# Crockoft-Walton_01.net
KiCad netlist of a schematic drawn in EAGLE
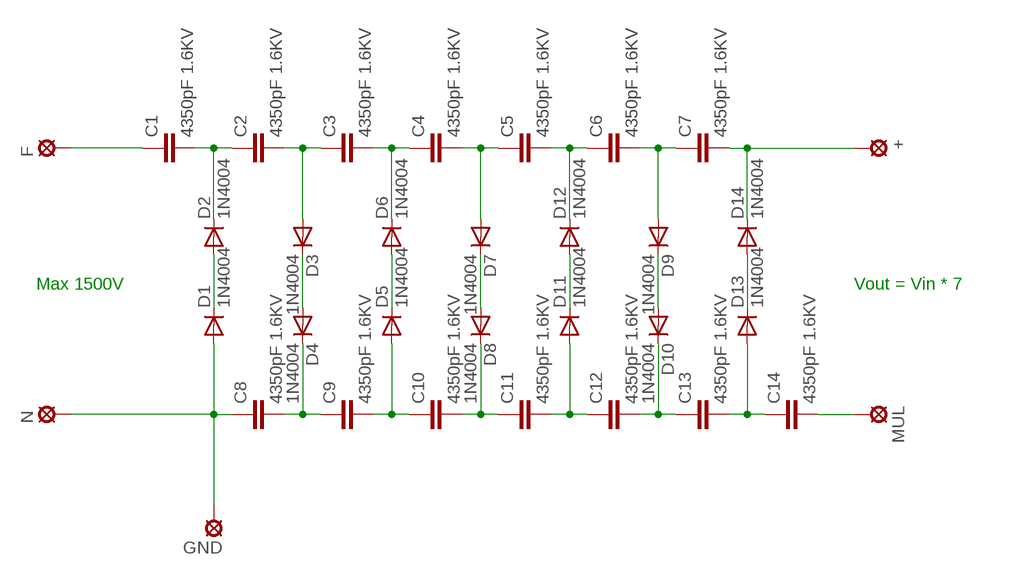
[diagram p0: schematic, sheet 1]

(export (version "E")
  (design (tool "Eeschema 10.0.6"))
  (components
    (comp (ref "+")
      (value "LSP13")
      (footprint "eagle-import:LSP13")
      (libsource (lib "eagle-import") (part "LSP13"))
    )
    (comp (ref "C1")
      (value "4350pF 1.6KV")
      (footprint "eagle-import:C225-074X268")
      (libsource (lib "eagle-import") (part "C-EU225-074X268"))
    )
    (comp (ref "C2")
      (value "4350pF 1.6KV")
      (footprint "eagle-import:C225-074X268")
      (libsource (lib "eagle-import") (part "C-EU225-074X268"))
    )
    (comp (ref "C3")
      (value "4350pF 1.6KV")
      (footprint "eagle-import:C225-074X268")
      (libsource (lib "eagle-import") (part "C-EU225-074X268"))
    )
    (comp (ref "C4")
      (value "4350pF 1.6KV")
      (footprint "eagle-import:C225-074X268")
      (libsource (lib "eagle-import") (part "C-EU225-074X268"))
    )
    (comp (ref "C5")
      (value "4350pF 1.6KV")
      (footprint "eagle-import:C225-074X268")
      (libsource (lib "eagle-import") (part "C-EU225-074X268"))
    )
    (comp (ref "C6")
      (value "4350pF 1.6KV")
      (footprint "eagle-import:C225-074X268")
      (libsource (lib "eagle-import") (part "C-EU225-074X268"))
    )
    (comp (ref "C7")
      (value "4350pF 1.6KV")
      (footprint "eagle-import:C225-074X268")
      (libsource (lib "eagle-import") (part "C-EU225-074X268"))
    )
    (comp (ref "C8")
      (value "4350pF 1.6KV")
      (footprint "eagle-import:C225-074X268")
      (libsource (lib "eagle-import") (part "C-EU225-074X268"))
    )
    (comp (ref "C9")
      (value "4350pF 1.6KV")
      (footprint "eagle-import:C225-074X268")
      (libsource (lib "eagle-import") (part "C-EU225-074X268"))
    )
    (comp (ref "C10")
      (value "4350pF 1.6KV")
      (footprint "eagle-import:C225-074X268")
      (libsource (lib "eagle-import") (part "C-EU225-074X268"))
    )
    (comp (ref "C11")
      (value "4350pF 1.6KV")
      (footprint "eagle-import:C225-074X268")
      (libsource (lib "eagle-import") (part "C-EU225-074X268"))
    )
    (comp (ref "C12")
      (value "4350pF 1.6KV")
      (footprint "eagle-import:C225-074X268")
      (libsource (lib "eagle-import") (part "C-EU225-074X268"))
    )
    (comp (ref "C13")
      (value "4350pF 1.6KV")
      (footprint "eagle-import:C225-074X268")
      (libsource (lib "eagle-import") (part "C-EU225-074X268"))
    )
    (comp (ref "C14")
      (value "4350pF 1.6KV")
      (footprint "eagle-import:C225-074X268")
      (libsource (lib "eagle-import") (part "C-EU225-074X268"))
    )
    (comp (ref "D1")
      (value "1N4004")
      (footprint "eagle-import:DO41-10")
      (libsource (lib "eagle-import") (part "1N4004"))
    )
    (comp (ref "D2")
      (value "1N4004")
      (footprint "eagle-import:DO41-10")
      (libsource (lib "eagle-import") (part "1N4004"))
    )
    (comp (ref "D3")
      (value "1N4004")
      (footprint "eagle-import:DO41-10")
      (libsource (lib "eagle-import") (part "1N4004"))
    )
    (comp (ref "D4")
      (value "1N4004")
      (footprint "eagle-import:DO41-10")
      (libsource (lib "eagle-import") (part "1N4004"))
    )
    (comp (ref "D5")
      (value "1N4004")
      (footprint "eagle-import:DO41-10")
      (libsource (lib "eagle-import") (part "1N4004"))
    )
    (comp (ref "D6")
      (value "1N4004")
      (footprint "eagle-import:DO41-10")
      (libsource (lib "eagle-import") (part "1N4004"))
    )
    (comp (ref "D7")
      (value "1N4004")
      (footprint "eagle-import:DO41-10")
      (libsource (lib "eagle-import") (part "1N4004"))
    )
    (comp (ref "D8")
      (value "1N4004")
      (footprint "eagle-import:DO41-10")
      (libsource (lib "eagle-import") (part "1N4004"))
    )
    (comp (ref "D9")
      (value "1N4004")
      (footprint "eagle-import:DO41-10")
      (libsource (lib "eagle-import") (part "1N4004"))
    )
    (comp (ref "D10")
      (value "1N4004")
      (footprint "eagle-import:DO41-10")
      (libsource (lib "eagle-import") (part "1N4004"))
    )
    (comp (ref "D11")
      (value "1N4004")
      (footprint "eagle-import:DO41-10")
      (libsource (lib "eagle-import") (part "1N4004"))
    )
    (comp (ref "D12")
      (value "1N4004")
      (footprint "eagle-import:DO41-10")
      (libsource (lib "eagle-import") (part "1N4004"))
    )
    (comp (ref "D13")
      (value "1N4004")
      (footprint "eagle-import:DO41-10")
      (libsource (lib "eagle-import") (part "1N4004"))
    )
    (comp (ref "D14")
      (value "1N4004")
      (footprint "eagle-import:DO41-10")
      (libsource (lib "eagle-import") (part "1N4004"))
    )
    (comp (ref "F")
      (value "LSP13")
      (footprint "eagle-import:LSP13")
      (libsource (lib "eagle-import") (part "LSP13"))
    )
    (comp (ref "GND")
      (value "LSP13")
      (footprint "eagle-import:LSP13")
      (libsource (lib "eagle-import") (part "LSP13"))
    )
    (comp (ref "MUL")
      (value "LSP13")
      (footprint "eagle-import:LSP13")
      (libsource (lib "eagle-import") (part "LSP13"))
    )
    (comp (ref "N")
      (value "LSP13")
      (footprint "eagle-import:LSP13")
      (libsource (lib "eagle-import") (part "LSP13"))
    )
  )
  (nets
    (net (code "1") (name "Net-(+-PadMP)") (class "Default")
      (node (ref "+") (pin "MP") (pinfunction "MP_MP") (pintype "passive"))
      (node (ref "C7") (pin "2") (pinfunction "2_2") (pintype "passive"))
      (node (ref "D14") (pin "C") (pinfunction "C_C") (pintype "passive"))
    )
    (net (code "2") (name "Net-(C1-Pad1)") (class "Default")
      (node (ref "C1") (pin "1") (pinfunction "1_1") (pintype "passive"))
      (node (ref "F") (pin "MP") (pinfunction "MP_MP") (pintype "passive"))
    )
    (net (code "3") (name "Net-(C1-Pad2)") (class "Default")
      (node (ref "C1") (pin "2") (pinfunction "2_2") (pintype "passive"))
      (node (ref "C2") (pin "1") (pinfunction "1_1") (pintype "passive"))
      (node (ref "D2") (pin "C") (pinfunction "C_C") (pintype "passive"))
    )
    (net (code "4") (name "Net-(C2-Pad2)") (class "Default")
      (node (ref "C2") (pin "2") (pinfunction "2_2") (pintype "passive"))
      (node (ref "C3") (pin "1") (pinfunction "1_1") (pintype "passive"))
      (node (ref "D3") (pin "A") (pinfunction "A_A") (pintype "passive"))
    )
    (net (code "5") (name "Net-(C3-Pad2)") (class "Default")
      (node (ref "C3") (pin "2") (pinfunction "2_2") (pintype "passive"))
      (node (ref "C4") (pin "1") (pinfunction "1_1") (pintype "passive"))
      (node (ref "D6") (pin "C") (pinfunction "C_C") (pintype "passive"))
    )
    (net (code "6") (name "Net-(C4-Pad2)") (class "Default")
      (node (ref "C4") (pin "2") (pinfunction "2_2") (pintype "passive"))
      (node (ref "C5") (pin "1") (pinfunction "1_1") (pintype "passive"))
      (node (ref "D7") (pin "A") (pinfunction "A_A") (pintype "passive"))
    )
    (net (code "7") (name "Net-(C5-Pad2)") (class "Default")
      (node (ref "C5") (pin "2") (pinfunction "2_2") (pintype "passive"))
      (node (ref "C6") (pin "1") (pinfunction "1_1") (pintype "passive"))
      (node (ref "D12") (pin "C") (pinfunction "C_C") (pintype "passive"))
    )
    (net (code "8") (name "Net-(C6-Pad2)") (class "Default")
      (node (ref "C6") (pin "2") (pinfunction "2_2") (pintype "passive"))
      (node (ref "C7") (pin "1") (pinfunction "1_1") (pintype "passive"))
      (node (ref "D9") (pin "A") (pinfunction "A_A") (pintype "passive"))
    )
    (net (code "9") (name "Net-(C8-Pad1)") (class "Default")
      (node (ref "C8") (pin "1") (pinfunction "1_1") (pintype "passive"))
      (node (ref "D1") (pin "A") (pinfunction "A_A") (pintype "passive"))
      (node (ref "GND") (pin "MP") (pinfunction "MP_MP") (pintype "passive"))
      (node (ref "N") (pin "MP") (pinfunction "MP_MP") (pintype "passive"))
    )
    (net (code "10") (name "Net-(C8-Pad2)") (class "Default")
      (node (ref "C8") (pin "2") (pinfunction "2_2") (pintype "passive"))
      (node (ref "C9") (pin "1") (pinfunction "1_1") (pintype "passive"))
      (node (ref "D4") (pin "C") (pinfunction "C_C") (pintype "passive"))
    )
    (net (code "11") (name "Net-(C10-Pad1)") (class "Default")
      (node (ref "C10") (pin "1") (pinfunction "1_1") (pintype "passive"))
      (node (ref "C9") (pin "2") (pinfunction "2_2") (pintype "passive"))
      (node (ref "D5") (pin "A") (pinfunction "A_A") (pintype "passive"))
    )
    (net (code "12") (name "Net-(C10-Pad2)") (class "Default")
      (node (ref "C10") (pin "2") (pinfunction "2_2") (pintype "passive"))
      (node (ref "C11") (pin "1") (pinfunction "1_1") (pintype "passive"))
      (node (ref "D8") (pin "C") (pinfunction "C_C") (pintype "passive"))
    )
    (net (code "13") (name "Net-(C11-Pad2)") (class "Default")
      (node (ref "C11") (pin "2") (pinfunction "2_2") (pintype "passive"))
      (node (ref "C12") (pin "1") (pinfunction "1_1") (pintype "passive"))
      (node (ref "D11") (pin "A") (pinfunction "A_A") (pintype "passive"))
    )
    (net (code "14") (name "Net-(C12-Pad2)") (class "Default")
      (node (ref "C12") (pin "2") (pinfunction "2_2") (pintype "passive"))
      (node (ref "C13") (pin "1") (pinfunction "1_1") (pintype "passive"))
      (node (ref "D10") (pin "C") (pinfunction "C_C") (pintype "passive"))
    )
    (net (code "15") (name "Net-(C13-Pad2)") (class "Default")
      (node (ref "C13") (pin "2") (pinfunction "2_2") (pintype "passive"))
      (node (ref "C14") (pin "1") (pinfunction "1_1") (pintype "passive"))
      (node (ref "D13") (pin "A") (pinfunction "A_A") (pintype "passive"))
    )
    (net (code "16") (name "Net-(C14-Pad2)") (class "Default")
      (node (ref "C14") (pin "2") (pinfunction "2_2") (pintype "passive"))
      (node (ref "MUL") (pin "MP") (pinfunction "MP_MP") (pintype "passive"))
    )
    (net (code "17") (name "Net-(D1-PadC)") (class "Default")
      (node (ref "D1") (pin "C") (pinfunction "C_C") (pintype "passive"))
      (node (ref "D2") (pin "A") (pinfunction "A_A") (pintype "passive"))
    )
    (net (code "18") (name "Net-(D3-PadC)") (class "Default")
      (node (ref "D3") (pin "C") (pinfunction "C_C") (pintype "passive"))
      (node (ref "D4") (pin "A") (pinfunction "A_A") (pintype "passive"))
    )
    (net (code "19") (name "Net-(D5-PadC)") (class "Default")
      (node (ref "D5") (pin "C") (pinfunction "C_C") (pintype "passive"))
      (node (ref "D6") (pin "A") (pinfunction "A_A") (pintype "passive"))
    )
    (net (code "20") (name "Net-(D7-PadC)") (class "Default")
      (node (ref "D7") (pin "C") (pinfunction "C_C") (pintype "passive"))
      (node (ref "D8") (pin "A") (pinfunction "A_A") (pintype "passive"))
    )
    (net (code "21") (name "Net-(D10-PadA)") (class "Default")
      (node (ref "D10") (pin "A") (pinfunction "A_A") (pintype "passive"))
      (node (ref "D9") (pin "C") (pinfunction "C_C") (pintype "passive"))
    )
    (net (code "22") (name "Net-(D11-PadC)") (class "Default")
      (node (ref "D11") (pin "C") (pinfunction "C_C") (pintype "passive"))
      (node (ref "D12") (pin "A") (pinfunction "A_A") (pintype "passive"))
    )
    (net (code "23") (name "Net-(D13-PadC)") (class "Default")
      (node (ref "D13") (pin "C") (pinfunction "C_C") (pintype "passive"))
      (node (ref "D14") (pin "A") (pinfunction "A_A") (pintype "passive"))
    )
  )
)
